# mcp4902.net
KiCad netlist of a schematic drawn in EAGLE
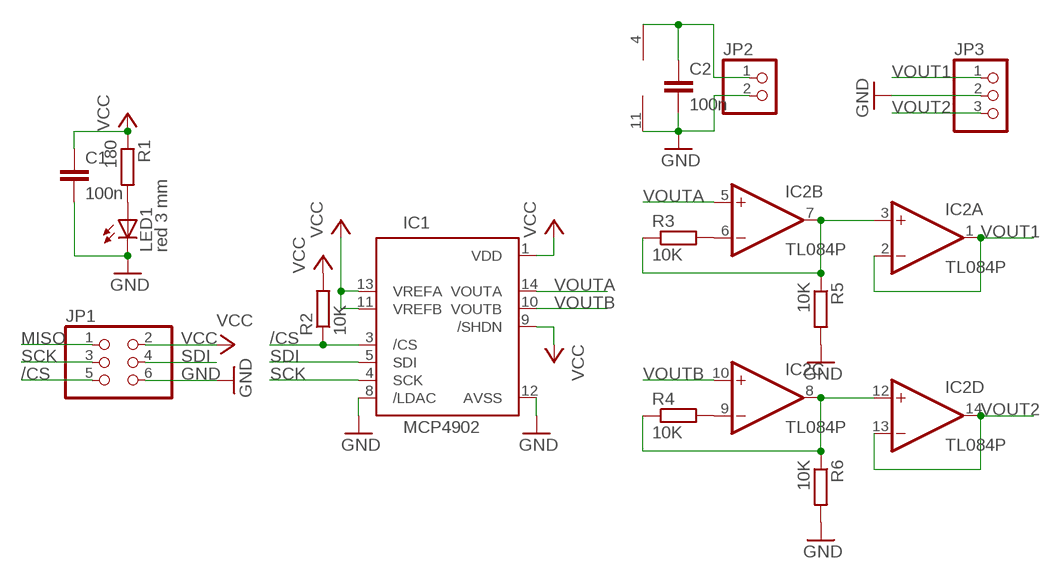
[diagram p0: schematic, sheet 1]

(export (version "E")
  (design (tool "Eeschema 10.0.6"))
  (components
    (comp (ref "C1")
      (value "100n")
      (footprint "eagle-import:C050-024X044")
      (libsource (lib "eagle-import") (part "C-EU050-024X044"))
    )
    (comp (ref "C2")
      (value "100n")
      (footprint "eagle-import:C050-024X044")
      (libsource (lib "eagle-import") (part "C-EU050-024X044"))
    )
    (comp (ref "IC1")
      (value "MCP4902")
      (footprint "eagle-import:DIL14")
      (libsource (lib "eagle-import") (part "MCP4922"))
    )
    (comp (ref "IC2")
      (value "TL084P")
      (footprint "eagle-import:DIL14")
      (libsource (lib "eagle-import") (part "TL084P"))
    )
    (comp (ref "JP1")
      (value "PINHD-2X3")
      (footprint "eagle-import:2X03")
      (libsource (lib "eagle-import") (part "PINHD-2X3"))
    )
    (comp (ref "JP2")
      (value "PINHD-1X2")
      (footprint "eagle-import:1X02")
      (libsource (lib "eagle-import") (part "PINHD-1X2"))
    )
    (comp (ref "JP3")
      (value "PINHD-1X3")
      (footprint "eagle-import:1X03")
      (libsource (lib "eagle-import") (part "PINHD-1X3"))
    )
    (comp (ref "LED1")
      (value "red 3 mm")
      (footprint "eagle-import:LED3MM")
      (libsource (lib "eagle-import") (part "LED3MM"))
    )
    (comp (ref "R1")
      (value "180")
      (footprint "eagle-import:0204V")
      (libsource (lib "eagle-import") (part "R-EU_0204/2V"))
    )
    (comp (ref "R2")
      (value "10K")
      (footprint "eagle-import:0204V")
      (libsource (lib "eagle-import") (part "R-EU_0204/2V"))
    )
    (comp (ref "R3")
      (value "10K")
      (footprint "eagle-import:0204V")
      (libsource (lib "eagle-import") (part "R-EU_0204/2V"))
    )
    (comp (ref "R4")
      (value "10K")
      (footprint "eagle-import:0204V")
      (libsource (lib "eagle-import") (part "R-EU_0204/2V"))
    )
    (comp (ref "R5")
      (value "10K")
      (footprint "eagle-import:0204V")
      (libsource (lib "eagle-import") (part "R-EU_0204/2V"))
    )
    (comp (ref "R6")
      (value "10K")
      (footprint "eagle-import:0204V")
      (libsource (lib "eagle-import") (part "R-EU_0204/2V"))
    )
  )
  (nets
    (net (code "1") (name "/MISO") (class "Default")
      (node (ref "JP1") (pin "1") (pinfunction "1_1") (pintype "passive"))
    )
    (net (code "2") (name "/SCK") (class "Default")
      (node (ref "IC1") (pin "4") (pinfunction "SCK_4") (pintype "input"))
      (node (ref "JP1") (pin "3") (pinfunction "3_3") (pintype "passive"))
    )
    (net (code "3") (name "/SDI") (class "Default")
      (node (ref "IC1") (pin "5") (pinfunction "SDI_5") (pintype "input"))
      (node (ref "JP1") (pin "4") (pinfunction "4_4") (pintype "passive"))
    )
    (net (code "4") (name "/VOUT1") (class "Default")
      (node (ref "IC2") (pin "1") (pinfunction "OUT_1") (pintype "output"))
      (node (ref "IC2") (pin "2") (pinfunction "-IN_2") (pintype "input"))
      (node (ref "JP3") (pin "1") (pinfunction "1_1") (pintype "passive"))
    )
    (net (code "5") (name "/VOUT2") (class "Default")
      (node (ref "IC2") (pin "13") (pinfunction "-IN_13") (pintype "input"))
      (node (ref "IC2") (pin "14") (pinfunction "OUT_14") (pintype "output"))
      (node (ref "JP3") (pin "3") (pinfunction "3_3") (pintype "passive"))
    )
    (net (code "6") (name "/VOUTA") (class "Default")
      (node (ref "IC1") (pin "14") (pinfunction "VOUTA_14") (pintype "output"))
      (node (ref "IC2") (pin "5") (pinfunction "+IN_5") (pintype "input"))
    )
    (net (code "7") (name "/VOUTB") (class "Default")
      (node (ref "IC1") (pin "10") (pinfunction "VOUTB_10") (pintype "output"))
      (node (ref "IC2") (pin "10") (pinfunction "+IN_10") (pintype "input"))
    )
    (net (code "8") (name "/{slash}CS") (class "Default")
      (node (ref "IC1") (pin "3") (pinfunction "/CS_3") (pintype "bidirectional"))
      (node (ref "JP1") (pin "5") (pinfunction "5_5") (pintype "passive"))
      (node (ref "R2") (pin "1") (pinfunction "1_1") (pintype "passive"))
    )
    (net (code "9") (name "GND") (class "Default")
      (node (ref "C1") (pin "2") (pinfunction "2_2") (pintype "passive"))
      (node (ref "C2") (pin "2") (pinfunction "2_2") (pintype "passive"))
      (node (ref "IC1") (pin "12") (pinfunction "AVSS_12") (pintype "power_in"))
      (node (ref "IC1") (pin "8") (pinfunction "/LDAC_8") (pintype "input"))
      (node (ref "IC2") (pin "11") (pinfunction "V-_11") (pintype "power_in"))
      (node (ref "JP1") (pin "6") (pinfunction "6_6") (pintype "passive"))
      (node (ref "JP2") (pin "2") (pinfunction "2_2") (pintype "passive"))
      (node (ref "JP3") (pin "2") (pinfunction "2_2") (pintype "passive"))
      (node (ref "LED1") (pin "K") (pinfunction "C_K") (pintype "passive"))
      (node (ref "R5") (pin "2") (pinfunction "2_2") (pintype "passive"))
      (node (ref "R6") (pin "2") (pinfunction "2_2") (pintype "passive"))
    )
    (net (code "10") (name "Net-(IC2A-+IN)") (class "Default")
      (node (ref "IC2") (pin "3") (pinfunction "+IN_3") (pintype "input"))
      (node (ref "IC2") (pin "7") (pinfunction "OUT_7") (pintype "output"))
      (node (ref "R3") (pin "1") (pinfunction "1_1") (pintype "passive"))
      (node (ref "R5") (pin "1") (pinfunction "1_1") (pintype "passive"))
    )
    (net (code "11") (name "Net-(IC2B--IN)") (class "Default")
      (node (ref "IC2") (pin "6") (pinfunction "-IN_6") (pintype "input"))
      (node (ref "R3") (pin "2") (pinfunction "2_2") (pintype "passive"))
    )
    (net (code "12") (name "Net-(IC2C--IN)") (class "Default")
      (node (ref "IC2") (pin "9") (pinfunction "-IN_9") (pintype "input"))
      (node (ref "R4") (pin "2") (pinfunction "2_2") (pintype "passive"))
    )
    (net (code "13") (name "Net-(IC2C-OUT)") (class "Default")
      (node (ref "IC2") (pin "12") (pinfunction "+IN_12") (pintype "input"))
      (node (ref "IC2") (pin "8") (pinfunction "OUT_8") (pintype "output"))
      (node (ref "R4") (pin "1") (pinfunction "1_1") (pintype "passive"))
      (node (ref "R6") (pin "1") (pinfunction "1_1") (pintype "passive"))
    )
    (net (code "14") (name "Net-(IC2E-V+)") (class "Default")
      (node (ref "C2") (pin "1") (pinfunction "1_1") (pintype "passive"))
      (node (ref "IC2") (pin "4") (pinfunction "V+_4") (pintype "power_in"))
      (node (ref "JP2") (pin "1") (pinfunction "1_1") (pintype "passive"))
    )
    (net (code "15") (name "Net-(LED1-PadA)") (class "Default")
      (node (ref "LED1") (pin "A") (pinfunction "A_A") (pintype "passive"))
      (node (ref "R1") (pin "2") (pinfunction "2_2") (pintype "passive"))
    )
    (net (code "16") (name "VCC") (class "Default")
      (node (ref "C1") (pin "1") (pinfunction "1_1") (pintype "passive"))
      (node (ref "IC1") (pin "1") (pinfunction "VDD_1") (pintype "power_in"))
      (node (ref "IC1") (pin "11") (pinfunction "VREFB_11") (pintype "bidirectional"))
      (node (ref "IC1") (pin "13") (pinfunction "VREFA_13") (pintype "input"))
      (node (ref "IC1") (pin "9") (pinfunction "/SHDN_9") (pintype "input"))
      (node (ref "JP1") (pin "2") (pinfunction "2_2") (pintype "passive"))
      (node (ref "R1") (pin "1") (pinfunction "1_1") (pintype "passive"))
      (node (ref "R2") (pin "2") (pinfunction "2_2") (pintype "passive"))
    )
  )
)
